# FE.net
KiCad netlist of a schematic drawn in Altium Designer
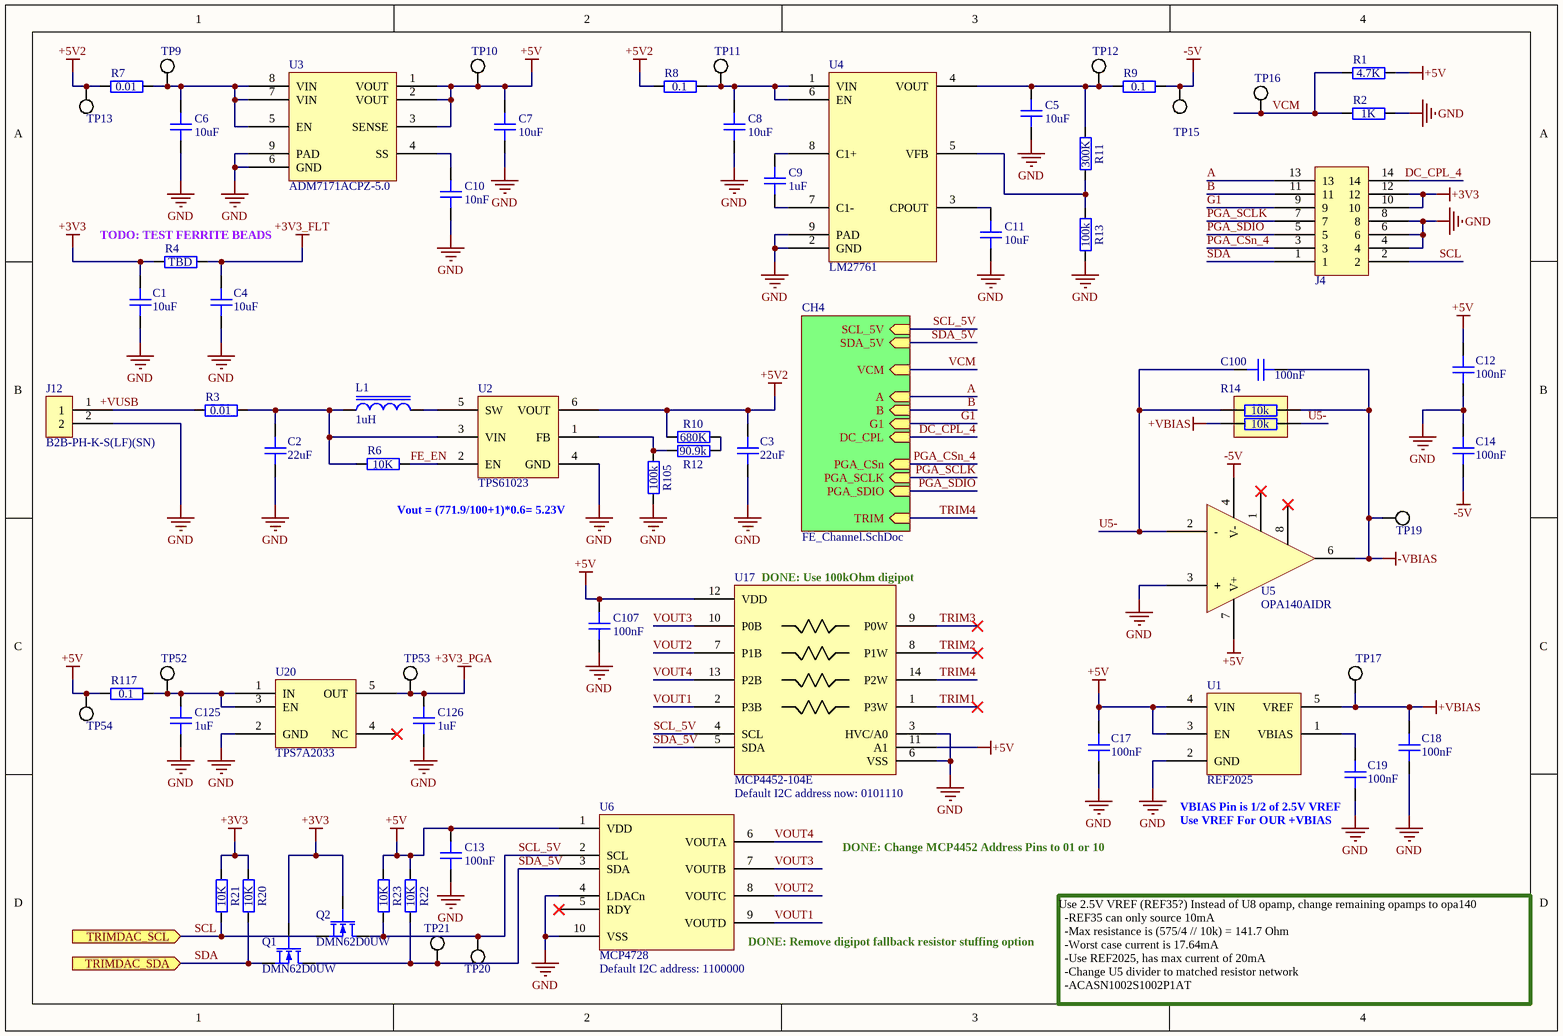
[diagram p0: FE.SchDoc]

(export (version "E")
  (design (tool "Eeschema 10.0.6"))
  (components
    (comp (ref "C1")
      (value "10uF")
      (footprint "GEN_C_0603")
      (fields
        (field (name "MANUFACTURER") "Murata")
        (field (name "HOUSE PART NUMBER") "C-10uF-0603-002")
        (field (name "MANUFACTURER PART NUMBER") "GRM188R61A106ME69D")
      )
      (libsource (lib "DSO") (part "CAP 10uF 10V X5R 0603"))
    )
    (comp (ref "C2")
      (value "22uF")
      (footprint "GEN_C_0805")
      (fields
        (field (name "HOUSE PART NUMBER") "C-22uF-0805-002")
        (field (name "MANUFACTURER") "Murata")
        (field (name "MANUFACTURER PART NUMBER") "GRM21BR61E226ME44L")
      )
      (libsource (lib "DSO") (part "CAP 22uF 25V X5R 0805"))
    )
    (comp (ref "C3")
      (value "22uF")
      (footprint "GEN_C_0805")
      (fields
        (field (name "HOUSE PART NUMBER") "C-22uF-0805-002")
        (field (name "MANUFACTURER") "Murata")
        (field (name "MANUFACTURER PART NUMBER") "GRM21BR61E226ME44L")
      )
      (libsource (lib "DSO") (part "CAP 22uF 25V X5R 0805"))
    )
    (comp (ref "C4")
      (value "10uF")
      (footprint "GEN_C_0603")
      (fields
        (field (name "MANUFACTURER") "Murata")
        (field (name "HOUSE PART NUMBER") "C-10uF-0603-002")
        (field (name "MANUFACTURER PART NUMBER") "GRM188R61A106ME69D")
      )
      (libsource (lib "DSO") (part "CAP 10uF 10V X5R 0603"))
    )
    (comp (ref "C5")
      (value "10uF")
      (footprint "GEN_C_0603")
      (fields
        (field (name "HOUSE PART NUMBER") "C-10uF-0603-002")
        (field (name "MANUFACTURER") "Murata")
        (field (name "MANUFACTURER PART NUMBER") "GRM188R61A106ME69D")
      )
      (libsource (lib "DSO") (part "CAP 10uF 10V X5R 0603"))
    )
    (comp (ref "C6")
      (value "10uF")
      (footprint "GEN_C_0603")
      (fields
        (field (name "HOUSE PART NUMBER") "C-10uF-0603-002")
        (field (name "MANUFACTURER") "Murata")
        (field (name "MANUFACTURER PART NUMBER") "GRM188R61A106ME69D")
      )
      (libsource (lib "DSO") (part "CAP 10uF 10V X5R 0603"))
    )
    (comp (ref "C7")
      (value "10uF")
      (footprint "GEN_C_0603")
      (fields
        (field (name "HOUSE PART NUMBER") "C-10uF-0603-002")
        (field (name "MANUFACTURER") "Murata")
        (field (name "MANUFACTURER PART NUMBER") "GRM188R61A106ME69D")
      )
      (libsource (lib "DSO") (part "CAP 10uF 10V X5R 0603"))
    )
    (comp (ref "C8")
      (value "10uF")
      (footprint "GEN_C_0603")
      (fields
        (field (name "HOUSE PART NUMBER") "C-10uF-0603-002")
        (field (name "MANUFACTURER") "Murata")
        (field (name "MANUFACTURER PART NUMBER") "GRM188R61A106ME69D")
      )
      (libsource (lib "DSO") (part "CAP 10uF 10V X5R 0603"))
    )
    (comp (ref "C9")
      (value "1uF")
      (footprint "GEN_C_0402")
      (fields
        (field (name "MANUFACTURER") "Murata")
        (field (name "MANUFACTURER PART NUMBER") "GRM155R61E105KA12D")
      )
      (libsource (lib "DSO") (part "CAP 1uF 25V X5R 0402"))
    )
    (comp (ref "C10")
      (value "10nF")
      (footprint "GEN_C_0402")
      (fields
        (field (name "MANUFACTURER") "Murata")
        (field (name "HOUSE PART NUMBER") "C-10nF-0402-002")
        (field (name "MANUFACTURER PART NUMBER") "GRM155R71H103KA88J")
      )
      (libsource (lib "DSO") (part "CAP 10nF 50V X7R 0402"))
    )
    (comp (ref "C11")
      (value "10uF")
      (footprint "GEN_C_0603")
      (fields
        (field (name "HOUSE PART NUMBER") "C-10uF-0603-002")
        (field (name "MANUFACTURER") "Murata")
        (field (name "MANUFACTURER PART NUMBER") "GRM188R61A106ME69D")
      )
      (libsource (lib "DSO") (part "CAP 10uF 10V X5R 0603"))
    )
    (comp (ref "C12")
      (value "100nF")
      (footprint "GEN_C_0402")
      (fields
        (field (name "HOUSE PART NUMBER") "C-100nF-0402-002")
        (field (name "MANUFACTURER") "Murata")
        (field (name "MANUFACTURER PART NUMBER") "GCM155R71C104KA55D")
      )
      (libsource (lib "DSO") (part "CAP 100nF 16V X7R 0402"))
    )
    (comp (ref "C13")
      (value "100nF")
      (footprint "GEN_C_0402")
      (fields
        (field (name "HOUSE PART NUMBER") "C-100nF-0402-002")
        (field (name "MANUFACTURER") "Murata")
        (field (name "MANUFACTURER PART NUMBER") "GCM155R71C104KA55D")
      )
      (libsource (lib "DSO") (part "CAP 100nF 16V X7R 0402"))
    )
    (comp (ref "C14")
      (value "100nF")
      (footprint "GEN_C_0402")
      (fields
        (field (name "HOUSE PART NUMBER") "C-100nF-0402-002")
        (field (name "MANUFACTURER") "Murata")
        (field (name "MANUFACTURER PART NUMBER") "GCM155R71C104KA55D")
      )
      (libsource (lib "DSO") (part "CAP 100nF 16V X7R 0402"))
    )
    (comp (ref "C17")
      (value "100nF")
      (footprint "GEN_C_0402")
      (fields
        (field (name "HOUSE PART NUMBER") "C-100nF-0402-002")
        (field (name "MANUFACTURER") "Murata")
        (field (name "MANUFACTURER PART NUMBER") "GCM155R71C104KA55D")
      )
      (libsource (lib "DSO") (part "CAP 100nF 16V X7R 0402"))
    )
    (comp (ref "C18")
      (value "100nF")
      (footprint "GEN_C_0402")
      (fields
        (field (name "HOUSE PART NUMBER") "C-100nF-0402-002")
        (field (name "MANUFACTURER") "Murata")
        (field (name "MANUFACTURER PART NUMBER") "GCM155R71C104KA55D")
      )
      (libsource (lib "DSO") (part "CAP 100nF 16V X7R 0402"))
    )
    (comp (ref "C19")
      (value "100nF")
      (footprint "GEN_C_0402")
      (fields
        (field (name "HOUSE PART NUMBER") "C-100nF-0402-002")
        (field (name "MANUFACTURER") "Murata")
        (field (name "MANUFACTURER PART NUMBER") "GCM155R71C104KA55D")
      )
      (libsource (lib "DSO") (part "CAP 100nF 16V X7R 0402"))
    )
    (comp (ref "C100")
      (value "100nF")
      (footprint "GEN_C_0402")
      (fields
        (field (name "HOUSE PART NUMBER") "C-100nF-0402-002")
        (field (name "MANUFACTURER") "Murata")
        (field (name "MANUFACTURER PART NUMBER") "GCM155R71C104KA55D")
      )
      (libsource (lib "DSO") (part "CAP 100nF 16V X7R 0402"))
    )
    (comp (ref "C107")
      (value "100nF")
      (footprint "GEN_C_0402")
      (fields
        (field (name "HOUSE PART NUMBER") "C-100nF-0402-002")
        (field (name "MANUFACTURER") "Murata")
        (field (name "MANUFACTURER PART NUMBER") "GCM155R71C104KA55D")
      )
      (libsource (lib "DSO") (part "CAP 100nF 16V X7R 0402"))
    )
    (comp (ref "C125")
      (value "1uF")
      (footprint "GEN_C_0402")
      (fields
        (field (name "MANUFACTURER") "Murata")
        (field (name "MANUFACTURER PART NUMBER") "GRM155R61E105KA12D")
      )
      (libsource (lib "DSO") (part "CAP 1uF 25V X5R 0402"))
    )
    (comp (ref "C126")
      (value "1uF")
      (footprint "GEN_C_0402")
      (fields
        (field (name "MANUFACTURER") "Murata")
        (field (name "MANUFACTURER PART NUMBER") "GRM155R61E105KA12D")
      )
      (libsource (lib "DSO") (part "CAP 1uF 25V X5R 0402"))
    )
    (comp (ref "J4")
      (value "2.54mm 2X7 Pin TH")
      (footprint "GEN_2.54mm_2X7_Pin_TH_RA")
      (libsource (lib "DSO") (part "CONN 2.54mm 2X7 Pin TH RA"))
    )
    (comp (ref "J12")
      (value "B2B-PH-K-S(LF)(SN)")
      (footprint "JST_B2B-PH-K-S(LF)(SN)")
      (fields
        (field (name "MANUFACTURER") "JST")
        (field (name "MANUFACTURER PART NUMBER") "B2B-PH-K-S-LF-SN")
      )
      (libsource (lib "DSO") (part "CONN JST PH 2 Pin TH"))
    )
    (comp (ref "L1")
      (value "1uH")
      (footprint "GEN_L_1210")
      (fields
        (field (name "MANUFACTURER") "Murata")
        (field (name "MANUFACTURER PART NUMBER") "1277AS-H-1R0M=P2")
      )
      (libsource (lib "DSO") (part "IND 1uH 3.1A 45 MOHM 1210"))
    )
    (comp (ref "Q1")
      (value "DMN62D0UW")
      (footprint "GEN_SOT_323")
      (fields (field (name "HOUSE PART NUMBER") "DMN62D0UW-7") (field (name "MANUFACTURER") "Diodes"))
      (libsource (lib "DSO") (part "NMOS DMN62D0UW"))
    )
    (comp (ref "Q2")
      (value "DMN62D0UW")
      (footprint "GEN_SOT_323")
      (fields (field (name "HOUSE PART NUMBER") "DMN62D0UW-7") (field (name "MANUFACTURER") "Diodes"))
      (libsource (lib "DSO") (part "NMOS DMN62D0UW"))
    )
    (comp (ref "R1")
      (value "4.7K")
      (footprint "GEN_R_0402")
      (fields
        (field (name "TOLERANCE") "1%")
        (field (name "MANUFACTURER") "Panasonic")
        (field (name "MANUFACTURER PART NUMBER") "ERJ-2RKF4701X")
      )
      (libsource (lib "DSO") (part "RES 4.7K OHM 1% 1/10W 0402"))
    )
    (comp (ref "R2")
      (value "1K")
      (footprint "GEN_R_0402")
      (fields
        (field (name "TOLERANCE") "1%")
        (field (name "MANUFACTURER") "Yageo")
        (field (name "HOUSE PART NUMBER") "R-1K-0402-1%-001")
      )
      (libsource (lib "DSO") (part "RES 1K OHM 1% 1/10W 0402"))
    )
    (comp (ref "R3")
      (value "0.01")
      (footprint "GEN_R_0603")
      (fields
        (field (name "TOLERANCE") "1%")
        (field (name "HOUSE PART NUMBER") "R-0.01-0603-1%-001")
        (field (name "MANUFACTURER") "Susumu")
      )
      (libsource (lib "DSO") (part "RES 0.01 OHM 1% 1/4W 0603"))
    )
    (comp (ref "R4") (value "TBD") (footprint "GEN_R_0603") (libsource (lib "DSO") (part "RES TBD 0603")))
    (comp (ref "R6")
      (value "10K")
      (footprint "GEN_R_0402")
      (fields
        (field (name "TOLERANCE") "1%")
        (field (name "MANUFACTURER") "Panasonic")
        (field (name "MANUFACTURER PART NUMBER") "ERJ-2RKF1002X")
      )
      (libsource (lib "") (part "RES 10K OHM 1% 1/10W 0402_1"))
    )
    (comp (ref "R7")
      (value "0.01")
      (footprint "GEN_R_0603")
      (fields
        (field (name "TOLERANCE") "1%")
        (field (name "HOUSE PART NUMBER") "R-0.01-0603-1%-001")
        (field (name "MANUFACTURER") "Susumu")
      )
      (libsource (lib "") (part "RES 0.01 OHM 1% 1/4W 0603_1"))
    )
    (comp (ref "R8")
      (value "0.1")
      (footprint "GEN_R_0402")
      (fields
        (field (name "TOLERANCE") "1%")
        (field (name "MANUFACTURER") "Panasonic")
        (field (name "MANUFACTURER PART NUMBER") "ERJ-2BSFR10X")
      )
      (libsource (lib "DSO") (part "RES 0.1 OHM 1% 1/6W 0402"))
    )
    (comp (ref "R9")
      (value "0.1")
      (footprint "GEN_R_0402")
      (fields
        (field (name "TOLERANCE") "1%")
        (field (name "MANUFACTURER") "Panasonic")
        (field (name "MANUFACTURER PART NUMBER") "ERJ-2BSFR10X")
      )
      (libsource (lib "DSO") (part "RES 0.1 OHM 1% 1/6W 0402"))
    )
    (comp (ref "R10")
      (value "680K")
      (footprint "GEN_R_0402")
      (fields
        (field (name "TOLERANCE") "1%")
        (field (name "MANUFACTURER") "Yageo")
        (field (name "MANUFACTURER PART NUMBER") "RC0402FR-07681KL")
      )
      (libsource (lib "DSO") (part "RES 680K OHM 1% 1/16W 0402"))
    )
    (comp (ref "R11")
      (value "300K")
      (footprint "GEN_R_0402")
      (fields
        (field (name "TOLERANCE") "1%")
        (field (name "MANUFACTURER") "Panasonic")
        (field (name "MANUFACTURER PART NUMBER") "ERJ-2RKF3003X")
      )
      (libsource (lib "DSO") (part "RES 300K OHM 1% 1/10W 0402"))
    )
    (comp (ref "R12")
      (value "90.9k")
      (footprint "GEN_R_0402")
      (fields
        (field (name "TOLERANCE") "1%")
        (field (name "MANUFACTURER") "Yageo")
        (field (name "MANUFACTURER PART NUMBER") "RC0402FR-0790K9L")
      )
      (libsource (lib "DSO") (part "RES 90.9K OHM 1% 1/16W 0402"))
    )
    (comp (ref "R13")
      (value "100k")
      (footprint "GEN_R_0402")
      (fields
        (field (name "TOLERANCE") "1%")
        (field (name "HOUSE PART NUMBER") "R-100K-0402-1%-001")
        (field (name "MANUFACTURER") "Yageo")
      )
      (libsource (lib "DSO") (part "RES 100K OHM 1% 1/10W 0402"))
    )
    (comp (ref "R14")
      (value "10K")
      (footprint "GEN_R_2ARRAY_0606")
      (fields
        (field (name "TOLERANCE") "1%")
        (field (name "MANUFACTURER") "Vishay Beyschlag")
        (field (name "MANUFACTURER PART NUMBER") "ACASN1002S1002P1ATF1002X")
      )
      (libsource (lib "DSO") (part "RES ARRAY 2x 10K OHM 0.05% 0606"))
    )
    (comp (ref "R20")
      (value "10K")
      (footprint "GEN_R_0402")
      (fields
        (field (name "TOLERANCE") "1%")
        (field (name "MANUFACTURER") "Panasonic")
        (field (name "MANUFACTURER PART NUMBER") "ERJ-2RKF1002X")
      )
      (libsource (lib "DSO") (part "RES 10K OHM 1% 1/10W 0402"))
    )
    (comp (ref "R21")
      (value "10K")
      (footprint "GEN_R_0402")
      (fields
        (field (name "TOLERANCE") "1%")
        (field (name "MANUFACTURER") "Panasonic")
        (field (name "MANUFACTURER PART NUMBER") "ERJ-2RKF1002X")
      )
      (libsource (lib "DSO") (part "RES 10K OHM 1% 1/10W 0402"))
    )
    (comp (ref "R22")
      (value "10K")
      (footprint "GEN_R_0402")
      (fields
        (field (name "TOLERANCE") "1%")
        (field (name "MANUFACTURER") "Panasonic")
        (field (name "MANUFACTURER PART NUMBER") "ERJ-2RKF1002X")
      )
      (libsource (lib "DSO") (part "RES 10K OHM 1% 1/10W 0402"))
    )
    (comp (ref "R23")
      (value "10K")
      (footprint "GEN_R_0402")
      (fields
        (field (name "TOLERANCE") "1%")
        (field (name "MANUFACTURER") "Panasonic")
        (field (name "MANUFACTURER PART NUMBER") "ERJ-2RKF1002X")
      )
      (libsource (lib "DSO") (part "RES 10K OHM 1% 1/10W 0402"))
    )
    (comp (ref "R105")
      (value "100k")
      (footprint "GEN_R_0402")
      (fields
        (field (name "TOLERANCE") "1%")
        (field (name "HOUSE PART NUMBER") "R-100K-0402-1%-001")
        (field (name "MANUFACTURER") "Yageo")
      )
      (libsource (lib "DSO") (part "RES 100K OHM 1% 1/10W 0402"))
    )
    (comp (ref "R117")
      (value "0.1")
      (footprint "GEN_R_0402")
      (fields
        (field (name "TOLERANCE") "1%")
        (field (name "MANUFACTURER") "Panasonic")
        (field (name "MANUFACTURER PART NUMBER") "ERJ-2BSFR10X")
      )
      (libsource (lib "DSO") (part "RES 0.1 OHM 1% 1/6W 0402"))
    )
    (comp (ref "TP9") (value "PCB") (footprint "GEN_TP_PCB") (libsource (lib "DSO") (part "TP PCB 1mm")))
    (comp (ref "TP10") (value "PCB") (footprint "GEN_TP_PCB") (libsource (lib "DSO") (part "TP PCB 1mm")))
    (comp (ref "TP11") (value "PCB") (footprint "GEN_TP_PCB") (libsource (lib "DSO") (part "TP PCB 1mm")))
    (comp (ref "TP12") (value "PCB") (footprint "GEN_TP_PCB") (libsource (lib "DSO") (part "TP PCB 1mm")))
    (comp (ref "TP13") (value "PCB") (footprint "GEN_TP_PCB") (libsource (lib "DSO") (part "TP PCB 1mm")))
    (comp (ref "TP15") (value "PCB") (footprint "GEN_TP_PCB") (libsource (lib "DSO") (part "TP PCB 1mm")))
    (comp (ref "TP16") (value "PCB") (footprint "GEN_TP_PCB") (libsource (lib "DSO") (part "TP PCB 1mm")))
    (comp (ref "TP17") (value "PCB") (footprint "GEN_TP_PCB") (libsource (lib "DSO") (part "TP PCB 1mm")))
    (comp (ref "TP19") (value "PCB") (footprint "GEN_TP_PCB") (libsource (lib "DSO") (part "TP PCB 1mm")))
    (comp (ref "TP20") (value "PCB") (footprint "GEN_TP_PCB") (libsource (lib "DSO") (part "TP PCB 1mm")))
    (comp (ref "TP21") (value "PCB") (footprint "GEN_TP_PCB") (libsource (lib "DSO") (part "TP PCB 1mm")))
    (comp (ref "TP52") (value "PCB") (footprint "GEN_TP_PCB") (libsource (lib "DSO") (part "TP PCB 1mm")))
    (comp (ref "TP53") (value "PCB") (footprint "GEN_TP_PCB") (libsource (lib "DSO") (part "TP PCB 1mm")))
    (comp (ref "TP54") (value "PCB") (footprint "GEN_TP_PCB") (libsource (lib "DSO") (part "TP PCB 1mm")))
    (comp (ref "U1")
      (value "REF2025")
      (footprint "GEN_SOT23_5_950_2900X1600X1450")
      (libsource (lib "DSO") (part "IC VREF REF2025"))
    )
    (comp (ref "U2")
      (value "TPS61023")
      (footprint "TI_SOT563_DRL0006A")
      (fields
        (field (name "MANUFACTURER") "Texas Instruments")
        (field (name "MANUFACTURER PART NUMBER") "TPS61023DRLT")
      )
      (libsource (lib "DSO") (part "IC BOOST TPS61023"))
    )
    (comp (ref "U3")
      (value "ADM7171ACPZ-5.0")
      (footprint "AD_DFN8_CP-8-21")
      (fields
        (field (name "MANUFACTURER") "Analog Devices")
        (field (name "MANUFACTURER PART NUMBER") "ADM7171ACPZ-5.0-R7")
      )
      (libsource (lib "DSO") (part "IC LDO ADM7171ACPZ-5.0"))
    )
    (comp (ref "U4")
      (value "LM27761")
      (footprint "TI_WSON8_DSG0008A")
      (fields
        (field (name "MANUFACTURER") "Texas Instruments")
        (field (name "MANUFACTURER PART NUMBER") "LM27761DSGR")
      )
      (libsource (lib "DSO") (part "IC CPUMP LM27761"))
    )
    (comp (ref "U5")
      (value "OPA140AIDR")
      (footprint "TI_SOIC8_D0008A")
      (fields (field (name "MANUFACTURER") "Texas Instruments"))
      (libsource (lib "DSO") (part "IC OPAMP OPA140"))
    )
    (comp (ref "U6")
      (value "MCP4728")
      (footprint "MC_MSOP10_UN")
      (fields (field (name "MANUFACTURER") "Microchip"))
      (libsource (lib "DSO") (part "IC DAC QUAD MCP4728"))
    )
    (comp (ref "U17")
      (value "MCP4452-104E")
      (footprint "MC_TSSOP14")
      (fields (field (name "MANUFACTURER") "Microchip"))
      (libsource (lib "DSO") (part "IC DIGIPOT QUAD MCP4452-104E"))
    )
    (comp (ref "U20")
      (value "TPS7A2033")
      (footprint "GEN_SOT23_5_950_2900X1600X1450")
      (fields
        (field (name "MANUFACTURER") "Texas Instruments")
        (field (name "MANUFACTURER PART NUMBER") "TPS7A2033PDBVR")
      )
      (libsource (lib "DSO") (part "IC LDO TPS7A2033"))
    )
  )
  (nets
    (net (code "1") (name "+3V3") (class "Default")
      (node (ref "C1") (pin "2") (pinfunction "2_2") (pintype "passive"))
      (node (ref "J4") (pin "10") (pinfunction "10_10") (pintype "passive"))
      (node (ref "J4") (pin "12") (pinfunction "12_12") (pintype "passive"))
      (node (ref "Q1") (pin "2") (pinfunction "G_2") (pintype "passive"))
      (node (ref "Q2") (pin "2") (pinfunction "G_2") (pintype "passive"))
      (node (ref "R20") (pin "2") (pinfunction "2_2") (pintype "passive"))
      (node (ref "R21") (pin "2") (pinfunction "2_2") (pintype "passive"))
      (node (ref "R4") (pin "1") (pinfunction "1_1") (pintype "passive"))
    )
    (net (code "2") (name "+3V3_FLT") (class "Default")
      (node (ref "C4") (pin "2") (pinfunction "2_2") (pintype "passive"))
      (node (ref "R4") (pin "2") (pinfunction "2_2") (pintype "passive"))
    )
    (net (code "3") (name "+3V3_PGA") (class "Default")
      (node (ref "C126") (pin "2") (pinfunction "2_2") (pintype "passive"))
      (node (ref "TP53") (pin "1") (pinfunction "1_1") (pintype "passive"))
      (node (ref "U20") (pin "5") (pinfunction "OUT_5") (pintype "power_in"))
    )
    (net (code "4") (name "+5V") (class "Default")
      (node (ref "C107") (pin "2") (pinfunction "2_2") (pintype "passive"))
      (node (ref "C12") (pin "1") (pinfunction "1_1") (pintype "passive"))
      (node (ref "C13") (pin "2") (pinfunction "2_2") (pintype "passive"))
      (node (ref "C17") (pin "1") (pinfunction "1_1") (pintype "passive"))
      (node (ref "C7") (pin "2") (pinfunction "2_2") (pintype "passive"))
      (node (ref "R1") (pin "2") (pinfunction "2_2") (pintype "passive"))
      (node (ref "R117") (pin "1") (pinfunction "1_1") (pintype "passive"))
      (node (ref "R22") (pin "2") (pinfunction "2_2") (pintype "passive"))
      (node (ref "R23") (pin "2") (pinfunction "2_2") (pintype "passive"))
      (node (ref "TP10") (pin "1") (pinfunction "1_1") (pintype "passive"))
      (node (ref "TP54") (pin "1") (pinfunction "1_1") (pintype "passive"))
      (node (ref "U1") (pin "3") (pinfunction "EN_3") (pintype "passive"))
      (node (ref "U1") (pin "4") (pinfunction "VIN_4") (pintype "passive"))
      (node (ref "U17") (pin "11") (pinfunction "A1_11") (pintype "passive"))
      (node (ref "U17") (pin "12") (pinfunction "VDD_12") (pintype "power_in"))
      (node (ref "U3") (pin "1") (pinfunction "VOUT_1") (pintype "power_in"))
      (node (ref "U3") (pin "2") (pinfunction "VOUT_2") (pintype "power_in"))
      (node (ref "U3") (pin "3") (pinfunction "SENSE_3") (pintype "passive"))
      (node (ref "U5") (pin "7") (pinfunction "V+_7") (pintype "passive"))
      (node (ref "U6") (pin "1") (pinfunction "VDD_1") (pintype "power_in"))
    )
    (net (code "5") (name "+5V2") (class "Default")
      (node (ref "C3") (pin "2") (pinfunction "2_2") (pintype "passive"))
      (node (ref "R10") (pin "2") (pinfunction "2_2") (pintype "passive"))
      (node (ref "R7") (pin "1") (pinfunction "1_1") (pintype "passive"))
      (node (ref "R8") (pin "1") (pinfunction "1_1") (pintype "passive"))
      (node (ref "TP13") (pin "1") (pinfunction "1_1") (pintype "passive"))
      (node (ref "U2") (pin "6") (pinfunction "VOUT_6") (pintype "passive"))
    )
    (net (code "6") (name "+VBIAS") (class "Default")
      (node (ref "C18") (pin "1") (pinfunction "1_1") (pintype "passive"))
      (node (ref "R14") (pin "2") (pinfunction "2_2") (pintype "passive"))
      (node (ref "TP17") (pin "1") (pinfunction "1_1") (pintype "passive"))
      (node (ref "U1") (pin "5") (pinfunction "VREF_5") (pintype "passive"))
    )
    (net (code "7") (name "-5V") (class "Default")
      (node (ref "C14") (pin "2") (pinfunction "2_2") (pintype "passive"))
      (node (ref "R9") (pin "2") (pinfunction "2_2") (pintype "passive"))
      (node (ref "TP15") (pin "1") (pinfunction "1_1") (pintype "passive"))
      (node (ref "U5") (pin "4") (pinfunction "V-_4") (pintype "passive"))
    )
    (net (code "8") (name "-VBIAS") (class "Default")
      (node (ref "C100") (pin "1") (pinfunction "1_1") (pintype "passive"))
      (node (ref "R14") (pin "4") (pinfunction "4_4") (pintype "passive"))
      (node (ref "TP19") (pin "1") (pinfunction "1_1") (pintype "passive"))
      (node (ref "U5") (pin "6") (pinfunction "OUT_6") (pintype "passive"))
    )
    (net (code "9") (name "/+VUSB") (class "Default")
      (node (ref "J12") (pin "1") (pinfunction "1_1") (pintype "passive"))
      (node (ref "R3") (pin "2") (pinfunction "2_2") (pintype "passive"))
    )
    (net (code "10") (name "/A") (class "Default")
      (node (ref "J4") (pin "13") (pinfunction "13_13") (pintype "passive"))
    )
    (net (code "11") (name "/B") (class "Default")
      (node (ref "J4") (pin "11") (pinfunction "11_11") (pintype "passive"))
    )
    (net (code "12") (name "/DC_CPL_4") (class "Default")
      (node (ref "J4") (pin "14") (pinfunction "14_14") (pintype "passive"))
    )
    (net (code "13") (name "/FE_EN") (class "Default")
      (node (ref "R6") (pin "1") (pinfunction "1_1") (pintype "passive"))
      (node (ref "U2") (pin "2") (pinfunction "EN_2") (pintype "passive"))
    )
    (net (code "14") (name "/G1") (class "Default")
      (node (ref "J4") (pin "9") (pinfunction "9_9") (pintype "passive"))
    )
    (net (code "15") (name "/PGA_CSn_4") (class "Default")
      (node (ref "J4") (pin "3") (pinfunction "3_3") (pintype "passive"))
    )
    (net (code "16") (name "/PGA_SCLK") (class "Default")
      (node (ref "J4") (pin "7") (pinfunction "7_7") (pintype "passive"))
    )
    (net (code "17") (name "/PGA_SDIO") (class "Default")
      (node (ref "J4") (pin "5") (pinfunction "5_5") (pintype "passive"))
    )
    (net (code "18") (name "/SCL") (class "Default")
      (node (ref "J4") (pin "2") (pinfunction "2_2") (pintype "passive"))
      (node (ref "Q2") (pin "3") (pinfunction "S_3") (pintype "passive"))
      (node (ref "R21") (pin "1") (pinfunction "1_1") (pintype "passive"))
    )
    (net (code "19") (name "/SCL_5V") (class "Default")
      (node (ref "Q2") (pin "1") (pinfunction "D_1") (pintype "passive"))
      (node (ref "R23") (pin "1") (pinfunction "1_1") (pintype "passive"))
      (node (ref "TP20") (pin "1") (pinfunction "1_1") (pintype "passive"))
      (node (ref "U17") (pin "4") (pinfunction "SCL_4") (pintype "passive"))
      (node (ref "U6") (pin "2") (pinfunction "SCL_2") (pintype "passive"))
    )
    (net (code "20") (name "/SDA") (class "Default")
      (node (ref "J4") (pin "1") (pinfunction "1_1") (pintype "passive"))
      (node (ref "Q1") (pin "3") (pinfunction "S_3") (pintype "passive"))
      (node (ref "R20") (pin "1") (pinfunction "1_1") (pintype "passive"))
    )
    (net (code "21") (name "/SDA_5V") (class "Default")
      (node (ref "Q1") (pin "1") (pinfunction "D_1") (pintype "passive"))
      (node (ref "R22") (pin "1") (pinfunction "1_1") (pintype "passive"))
      (node (ref "TP21") (pin "1") (pinfunction "1_1") (pintype "passive"))
      (node (ref "U17") (pin "5") (pinfunction "SDA_5") (pintype "passive"))
      (node (ref "U6") (pin "3") (pinfunction "SDA_3") (pintype "passive"))
    )
    (net (code "22") (name "/TRIM1") (class "Default")
      (node (ref "U17") (pin "1") (pinfunction "P3W_1") (pintype "passive+no_connect"))
    )
    (net (code "23") (name "/TRIM2") (class "Default")
      (node (ref "U17") (pin "8") (pinfunction "P1W_8") (pintype "passive+no_connect"))
    )
    (net (code "24") (name "/TRIM3") (class "Default")
      (node (ref "U17") (pin "9") (pinfunction "P0W_9") (pintype "passive+no_connect"))
    )
    (net (code "25") (name "/TRIM4") (class "Default")
      (node (ref "U17") (pin "14") (pinfunction "P2W_14") (pintype "passive"))
    )
    (net (code "26") (name "/U5-") (class "Default")
      (node (ref "C100") (pin "2") (pinfunction "2_2") (pintype "passive"))
      (node (ref "R14") (pin "1") (pinfunction "1_1") (pintype "passive"))
      (node (ref "R14") (pin "3") (pinfunction "3_3") (pintype "passive"))
      (node (ref "U5") (pin "2") (pinfunction "-_2") (pintype "passive"))
    )
    (net (code "27") (name "/VCM") (class "Default")
      (node (ref "R1") (pin "1") (pinfunction "1_1") (pintype "passive"))
      (node (ref "R2") (pin "1") (pinfunction "1_1") (pintype "passive"))
      (node (ref "TP16") (pin "1") (pinfunction "1_1") (pintype "passive"))
    )
    (net (code "28") (name "/VOUT1") (class "Default")
      (node (ref "U17") (pin "2") (pinfunction "P3B_2") (pintype "passive"))
      (node (ref "U6") (pin "9") (pinfunction "VOUTD_9") (pintype "passive"))
    )
    (net (code "29") (name "/VOUT2") (class "Default")
      (node (ref "U17") (pin "7") (pinfunction "P1B_7") (pintype "passive"))
      (node (ref "U6") (pin "8") (pinfunction "VOUTC_8") (pintype "passive"))
    )
    (net (code "30") (name "/VOUT3") (class "Default")
      (node (ref "U17") (pin "10") (pinfunction "P0B_10") (pintype "passive"))
      (node (ref "U6") (pin "7") (pinfunction "VOUTB_7") (pintype "passive"))
    )
    (net (code "31") (name "/VOUT4") (class "Default")
      (node (ref "U17") (pin "13") (pinfunction "P2B_13") (pintype "passive"))
      (node (ref "U6") (pin "6") (pinfunction "VOUTA_6") (pintype "passive"))
    )
    (net (code "32") (name "GND") (class "Default")
      (node (ref "C1") (pin "1") (pinfunction "1_1") (pintype "passive"))
      (node (ref "C10") (pin "1") (pinfunction "1_1") (pintype "passive"))
      (node (ref "C107") (pin "1") (pinfunction "1_1") (pintype "passive"))
      (node (ref "C11") (pin "1") (pinfunction "1_1") (pintype "passive"))
      (node (ref "C12") (pin "2") (pinfunction "2_2") (pintype "passive"))
      (node (ref "C125") (pin "1") (pinfunction "1_1") (pintype "passive"))
      (node (ref "C126") (pin "1") (pinfunction "1_1") (pintype "passive"))
      (node (ref "C13") (pin "1") (pinfunction "1_1") (pintype "passive"))
      (node (ref "C14") (pin "1") (pinfunction "1_1") (pintype "passive"))
      (node (ref "C17") (pin "2") (pinfunction "2_2") (pintype "passive"))
      (node (ref "C18") (pin "2") (pinfunction "2_2") (pintype "passive"))
      (node (ref "C19") (pin "1") (pinfunction "1_1") (pintype "passive"))
      (node (ref "C2") (pin "1") (pinfunction "1_1") (pintype "passive"))
      (node (ref "C3") (pin "1") (pinfunction "1_1") (pintype "passive"))
      (node (ref "C4") (pin "1") (pinfunction "1_1") (pintype "passive"))
      (node (ref "C5") (pin "1") (pinfunction "1_1") (pintype "passive"))
      (node (ref "C6") (pin "1") (pinfunction "1_1") (pintype "passive"))
      (node (ref "C7") (pin "1") (pinfunction "1_1") (pintype "passive"))
      (node (ref "C8") (pin "1") (pinfunction "1_1") (pintype "passive"))
      (node (ref "J12") (pin "2") (pinfunction "2_2") (pintype "passive"))
      (node (ref "J4") (pin "4") (pinfunction "4_4") (pintype "passive"))
      (node (ref "J4") (pin "6") (pinfunction "6_6") (pintype "passive"))
      (node (ref "J4") (pin "8") (pinfunction "8_8") (pintype "passive"))
      (node (ref "R105") (pin "1") (pinfunction "1_1") (pintype "passive"))
      (node (ref "R13") (pin "1") (pinfunction "1_1") (pintype "passive"))
      (node (ref "R2") (pin "2") (pinfunction "2_2") (pintype "passive"))
      (node (ref "U1") (pin "2") (pinfunction "GND_2") (pintype "passive"))
      (node (ref "U17") (pin "3") (pinfunction "HVC/A0_3") (pintype "passive"))
      (node (ref "U17") (pin "6") (pinfunction "VSS_6") (pintype "power_in"))
      (node (ref "U2") (pin "4") (pinfunction "GND_4") (pintype "power_in"))
      (node (ref "U20") (pin "2") (pinfunction "GND_2") (pintype "power_in"))
      (node (ref "U3") (pin "6") (pinfunction "GND_6") (pintype "power_in"))
      (node (ref "U3") (pin "9") (pinfunction "PAD_9") (pintype "passive"))
      (node (ref "U4") (pin "2") (pinfunction "GND_2") (pintype "power_in"))
      (node (ref "U4") (pin "9") (pinfunction "PAD_9") (pintype "power_in"))
      (node (ref "U5") (pin "3") (pinfunction "+_3") (pintype "passive"))
      (node (ref "U6") (pin "10") (pinfunction "VSS_10") (pintype "power_in"))
      (node (ref "U6") (pin "4") (pinfunction "LDACn_4") (pintype "passive"))
    )
    (net (code "33") (name "Net-(R10-Pad1)") (class "Default")
      (node (ref "R10") (pin "1") (pinfunction "1_1") (pintype "passive"))
      (node (ref "R12") (pin "2") (pinfunction "2_2") (pintype "passive"))
    )
    (net (code "34") (name "Net-(U1-VBIAS)") (class "Default")
      (node (ref "C19") (pin "2") (pinfunction "2_2") (pintype "passive"))
      (node (ref "U1") (pin "1") (pinfunction "VBIAS_1") (pintype "power_in"))
    )
    (net (code "35") (name "Net-(U2-FB)") (class "Default")
      (node (ref "R105") (pin "2") (pinfunction "2_2") (pintype "passive"))
      (node (ref "R12") (pin "1") (pinfunction "1_1") (pintype "passive"))
      (node (ref "U2") (pin "1") (pinfunction "FB_1") (pintype "passive"))
    )
    (net (code "36") (name "Net-(U2-SW)") (class "Default")
      (node (ref "L1") (pin "2") (pinfunction "2_2") (pintype "passive"))
      (node (ref "U2") (pin "5") (pinfunction "SW_5") (pintype "passive"))
    )
    (net (code "37") (name "Net-(U2-VIN)") (class "Default")
      (node (ref "C2") (pin "2") (pinfunction "2_2") (pintype "passive"))
      (node (ref "L1") (pin "1") (pinfunction "1_1") (pintype "passive"))
      (node (ref "R3") (pin "1") (pinfunction "1_1") (pintype "passive"))
      (node (ref "R6") (pin "2") (pinfunction "2_2") (pintype "passive"))
      (node (ref "U2") (pin "3") (pinfunction "VIN_3") (pintype "power_in"))
    )
    (net (code "38") (name "Net-(U3-EN)") (class "Default")
      (node (ref "C6") (pin "2") (pinfunction "2_2") (pintype "passive"))
      (node (ref "R7") (pin "2") (pinfunction "2_2") (pintype "passive"))
      (node (ref "TP9") (pin "1") (pinfunction "1_1") (pintype "passive"))
      (node (ref "U3") (pin "5") (pinfunction "EN_5") (pintype "passive"))
      (node (ref "U3") (pin "7") (pinfunction "VIN_7") (pintype "power_in"))
      (node (ref "U3") (pin "8") (pinfunction "VIN_8") (pintype "power_in"))
    )
    (net (code "39") (name "Net-(U3-SS)") (class "Default")
      (node (ref "C10") (pin "2") (pinfunction "2_2") (pintype "passive"))
      (node (ref "U3") (pin "4") (pinfunction "SS_4") (pintype "passive"))
    )
    (net (code "40") (name "Net-(U4-C1+)") (class "Default")
      (node (ref "C9") (pin "2") (pinfunction "2_2") (pintype "passive"))
      (node (ref "U4") (pin "8") (pinfunction "C1+_8") (pintype "passive"))
    )
    (net (code "41") (name "Net-(U4-C1-)") (class "Default")
      (node (ref "C9") (pin "1") (pinfunction "1_1") (pintype "passive"))
      (node (ref "U4") (pin "7") (pinfunction "C1-_7") (pintype "passive"))
    )
    (net (code "42") (name "Net-(U4-CPOUT)") (class "Default")
      (node (ref "C11") (pin "2") (pinfunction "2_2") (pintype "passive"))
      (node (ref "U4") (pin "3") (pinfunction "CPOUT_3") (pintype "passive"))
    )
    (net (code "43") (name "Net-(U4-EN)") (class "Default")
      (node (ref "C8") (pin "2") (pinfunction "2_2") (pintype "passive"))
      (node (ref "R8") (pin "2") (pinfunction "2_2") (pintype "passive"))
      (node (ref "TP11") (pin "1") (pinfunction "1_1") (pintype "passive"))
      (node (ref "U4") (pin "1") (pinfunction "VIN_1") (pintype "power_in"))
      (node (ref "U4") (pin "6") (pinfunction "EN_6") (pintype "passive"))
    )
    (net (code "44") (name "Net-(U4-VFB)") (class "Default")
      (node (ref "R11") (pin "1") (pinfunction "1_1") (pintype "passive"))
      (node (ref "R13") (pin "2") (pinfunction "2_2") (pintype "passive"))
      (node (ref "U4") (pin "5") (pinfunction "VFB_5") (pintype "passive"))
    )
    (net (code "45") (name "Net-(U4-VOUT)") (class "Default")
      (node (ref "C5") (pin "2") (pinfunction "2_2") (pintype "passive"))
      (node (ref "R11") (pin "2") (pinfunction "2_2") (pintype "passive"))
      (node (ref "R9") (pin "1") (pinfunction "1_1") (pintype "passive"))
      (node (ref "TP12") (pin "1") (pinfunction "1_1") (pintype "passive"))
      (node (ref "U4") (pin "4") (pinfunction "VOUT_4") (pintype "power_in"))
    )
    (net (code "46") (name "Net-(U20-EN)") (class "Default")
      (node (ref "C125") (pin "2") (pinfunction "2_2") (pintype "passive"))
      (node (ref "R117") (pin "2") (pinfunction "2_2") (pintype "passive"))
      (node (ref "TP52") (pin "1") (pinfunction "1_1") (pintype "passive"))
      (node (ref "U20") (pin "1") (pinfunction "IN_1") (pintype "power_in"))
      (node (ref "U20") (pin "3") (pinfunction "EN_3") (pintype "passive"))
    )
    (net (code "47") (name "unconnected-(U5-N1-Pad1)") (class "Default")
      (node (ref "U5") (pin "1") (pinfunction "N1_1") (pintype "passive+no_connect"))
    )
    (net (code "48") (name "unconnected-(U5-N2-Pad8)") (class "Default")
      (node (ref "U5") (pin "8") (pinfunction "N2_8") (pintype "passive+no_connect"))
    )
    (net (code "49") (name "unconnected-(U6-RDY-Pad5)") (class "Default")
      (node (ref "U6") (pin "5") (pinfunction "RDY_5") (pintype "passive+no_connect"))
    )
    (net (code "50") (name "unconnected-(U20-NC-Pad4)") (class "Default")
      (node (ref "U20") (pin "4") (pinfunction "NC_4") (pintype "passive+no_connect"))
    )
  )
)
